# 02_CMUT_RX.net
KiCad netlist of a schematic drawn in Altium Designer
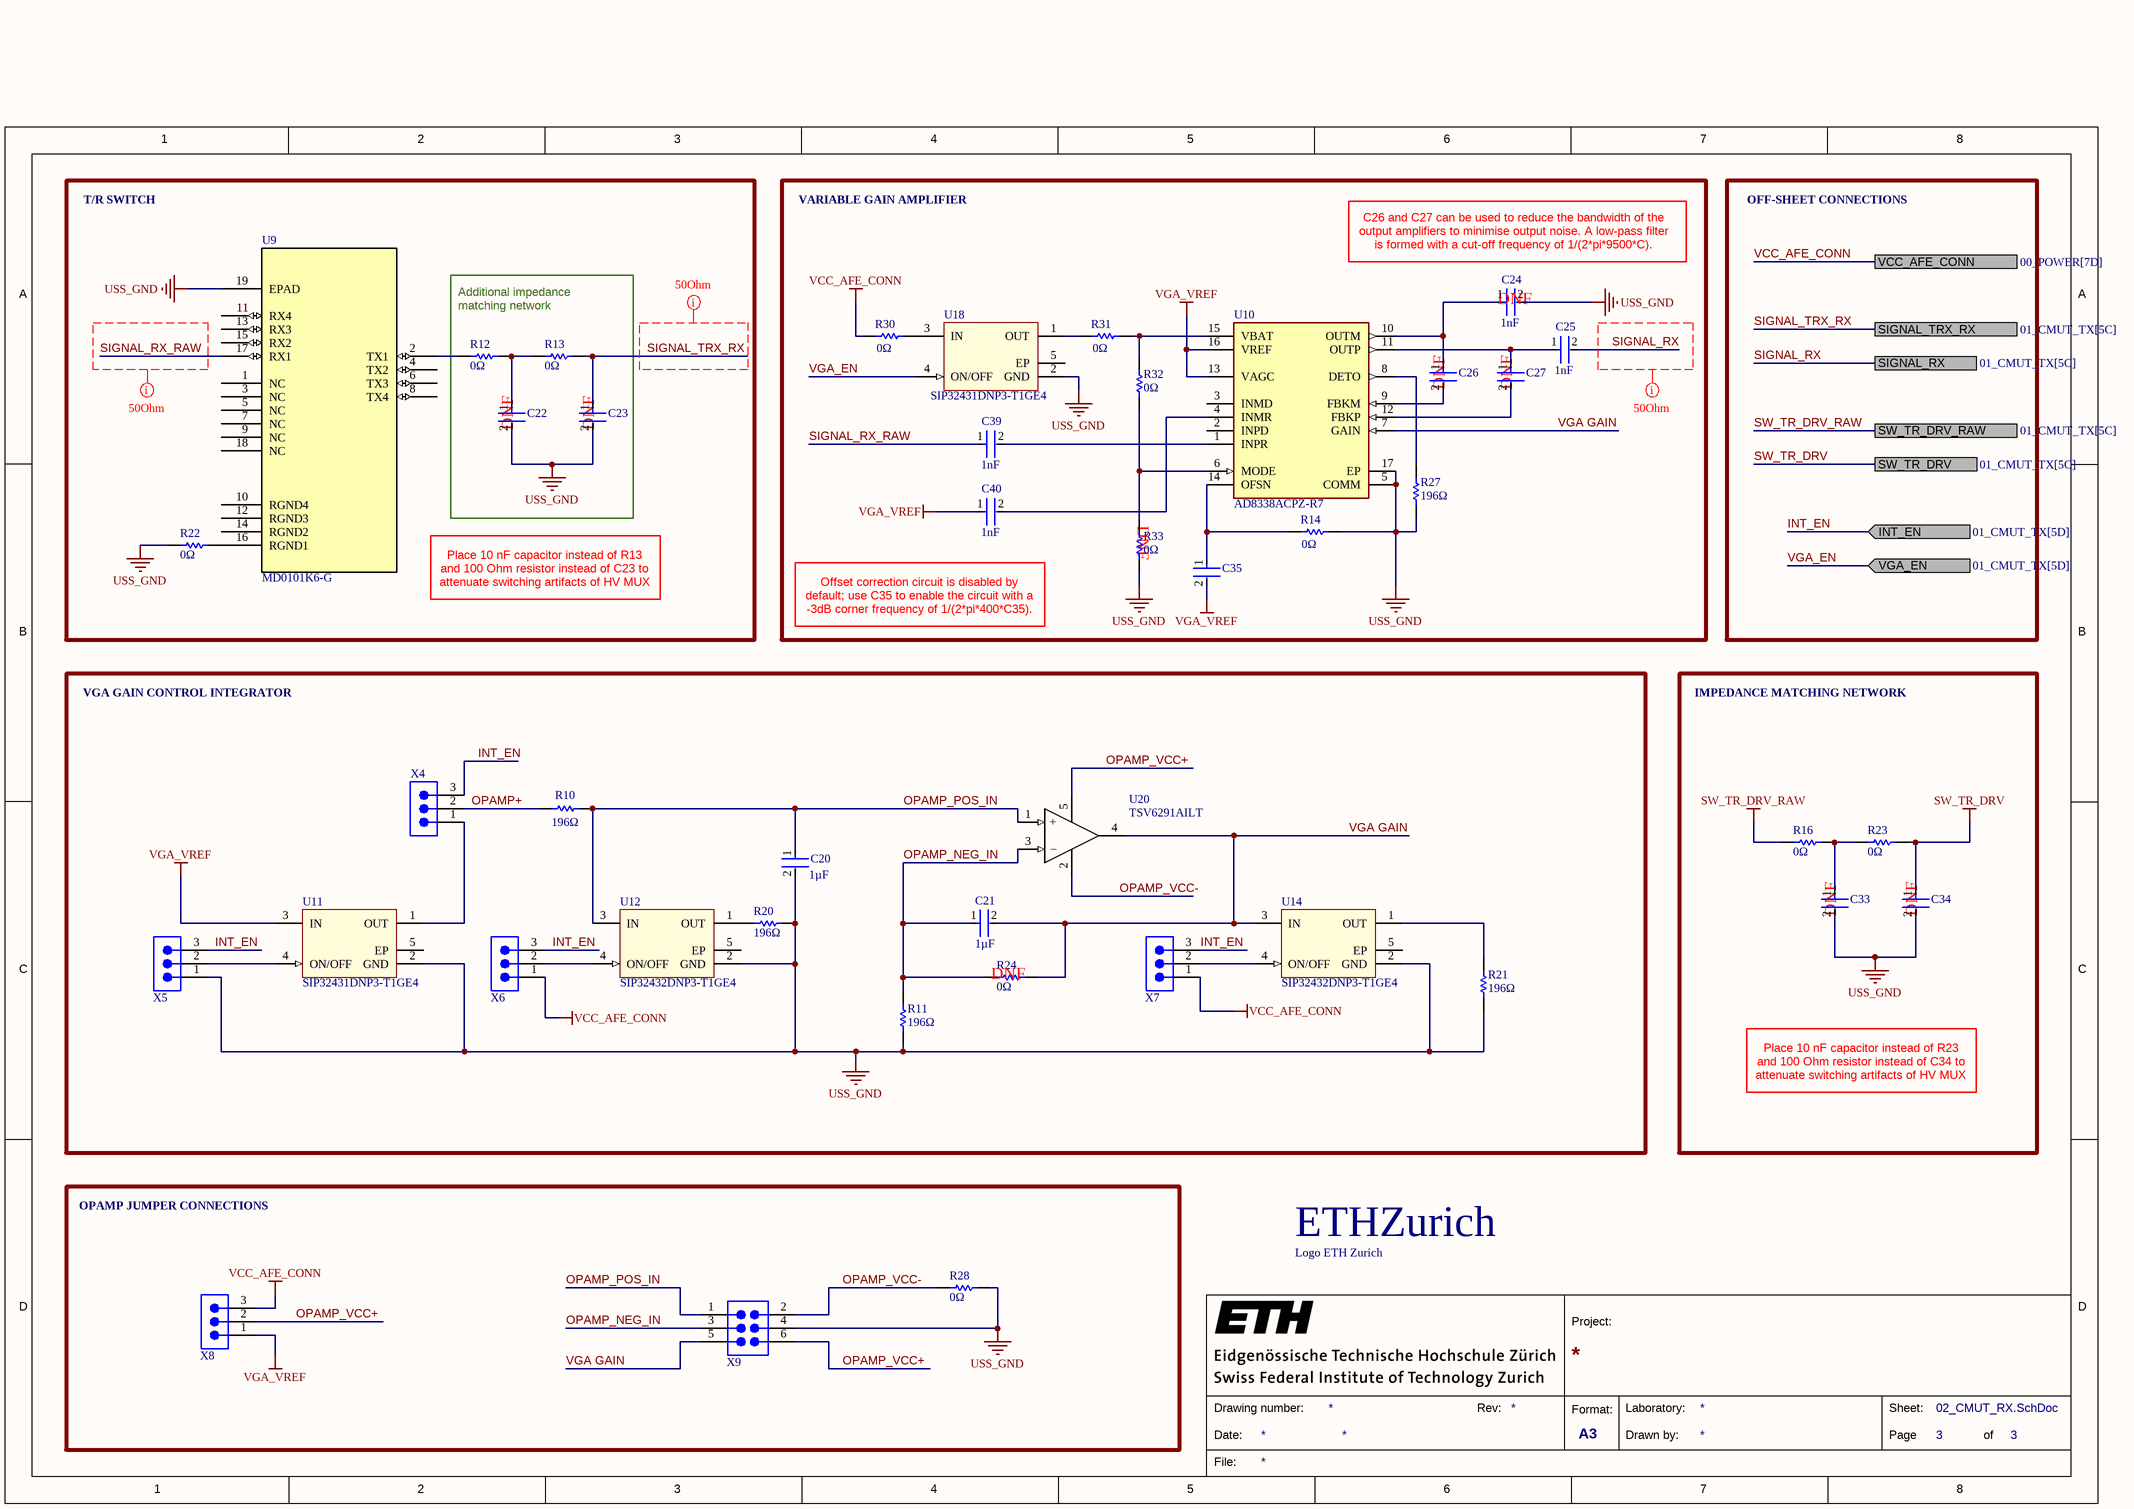
[diagram p0: 02_CMUT_RX.SchDoc]

(export (version "E")
  (design (tool "Eeschema 10.0.6"))
  (components
    (comp (ref "A1")
      (value "Logo ETH Zurich")
      (footprint "eth-zurich_4mm")
      (libsource (lib "ETHZ Vault") (part "Logo ETH Zurich"))
    )
    (comp (ref "C20")
      (value "CGA3E3X5R1H105K")
      (footprint "FP-CGA3E-0_3-0_1-IPC_B")
      (description "Cap Ceramic 1uF 50V X5R 10% Pad SMD 0603 +85°C Automotive T/R")
      (fields (field (name "TOLERANCE") "10%") (field (name "CAPACITANCE") "1µF"))
      (libsource (lib "Altium Content Vault") (part "b4654b650e69147ec39a6b967a45e02"))
    )
    (comp (ref "C21")
      (value "CGA3E3X5R1H105K")
      (footprint "FP-CGA3E-0_3-0_1-IPC_B")
      (description "Cap Ceramic 1uF 50V X5R 10% Pad SMD 0603 +85°C Automotive T/R")
      (fields (field (name "TOLERANCE") "10%") (field (name "CAPACITANCE") "1µF"))
      (libsource (lib "Altium Content Vault") (part "b4654b650e69147ec39a6b967a45e02"))
    )
    (comp (ref "C22")
      (value "CGA3E3X5R1H105K")
      (footprint "FP-CGA3E-0_3-0_1-IPC_B")
      (description "Cap Ceramic 1uF 50V X5R 10% Pad SMD 0603 +85°C Automotive T/R")
      (fields (field (name "TOLERANCE") "10%"))
      (libsource (lib "Altium Content Vault") (part "b4654b650e69147ec39a6b967a45e02"))
    )
    (comp (ref "C23")
      (value "CGA3E3X5R1H105K")
      (footprint "FP-CGA3E-0_3-0_1-IPC_B")
      (description "Cap Ceramic 1uF 50V X5R 10% Pad SMD 0603 +85°C Automotive T/R")
      (fields (field (name "TOLERANCE") "10%"))
      (libsource (lib "Altium Content Vault") (part "b4654b650e69147ec39a6b967a45e02"))
    )
    (comp (ref "C24")
      (value "TDK CGA3E2X5R1H102K080AA")
      (footprint "FP-CGA3E-0_3-0_1-IPC_A")
      (description "Cap Ceramic 1nF 50V X5R 10% Pad SMD 0603 +85°C Automotive T/R")
      (fields (field (name "TOLERANCE") "10%") (field (name "CAPACITANCE") "1nF"))
      (libsource (lib "Altium Content Vault") (part "b4654b650e69147ec39a6b967a45e02"))
    )
    (comp (ref "C25")
      (value "TDK CGA3E2X5R1H102K080AA")
      (footprint "FP-CGA3E-0_3-0_1-IPC_A")
      (description "Cap Ceramic 1nF 50V X5R 10% Pad SMD 0603 +85°C Automotive T/R")
      (fields (field (name "TOLERANCE") "10%") (field (name "CAPACITANCE") "1nF"))
      (libsource (lib "Altium Content Vault") (part "b4654b650e69147ec39a6b967a45e02"))
    )
    (comp (ref "C26")
      (value "CGA3E3X5R1H105K")
      (footprint "FP-CGA3E-0_3-0_1-IPC_B")
      (description "Cap Ceramic 1uF 50V X5R 10% Pad SMD 0603 +85°C Automotive T/R")
      (fields (field (name "TOLERANCE") "10%"))
      (libsource (lib "Altium Content Vault") (part "b4654b650e69147ec39a6b967a45e02"))
    )
    (comp (ref "C27")
      (value "CGA3E3X5R1H105K")
      (footprint "FP-CGA3E-0_3-0_1-IPC_B")
      (description "Cap Ceramic 1uF 50V X5R 10% Pad SMD 0603 +85°C Automotive T/R")
      (fields (field (name "TOLERANCE") "10%"))
      (libsource (lib "Altium Content Vault") (part "b4654b650e69147ec39a6b967a45e02"))
    )
    (comp (ref "C33")
      (value "CGA3E3X5R1H105K")
      (footprint "FP-CGA3E-0_3-0_1-IPC_B")
      (description "Cap Ceramic 1uF 50V X5R 10% Pad SMD 0603 +85°C Automotive T/R")
      (fields (field (name "TOLERANCE") "10%"))
      (libsource (lib "Altium Content Vault") (part "b4654b650e69147ec39a6b967a45e02"))
    )
    (comp (ref "C34")
      (value "CGA3E3X5R1H105K")
      (footprint "FP-CGA3E-0_3-0_1-IPC_B")
      (description "Cap Ceramic 1uF 50V X5R 10% Pad SMD 0603 +85°C Automotive T/R")
      (fields (field (name "TOLERANCE") "10%"))
      (libsource (lib "Altium Content Vault") (part "b4654b650e69147ec39a6b967a45e02"))
    )
    (comp (ref "C35")
      (value "CGA3E3X5R1H105K")
      (footprint "FP-CGA3E-0_3-0_1-IPC_B")
      (description "Cap Ceramic 1uF 50V X5R 10% Pad SMD 0603 +85°C Automotive T/R")
      (fields (field (name "TOLERANCE") "10%"))
      (libsource (lib "Altium Content Vault") (part "b4654b650e69147ec39a6b967a45e02"))
    )
    (comp (ref "C39")
      (value "TDK CGA3E2X5R1H102K080AA")
      (footprint "FP-CGA3E-0_3-0_1-IPC_A")
      (description "Cap Ceramic 1nF 50V X5R 10% Pad SMD 0603 +85°C Automotive T/R")
      (fields (field (name "TOLERANCE") "10%") (field (name "CAPACITANCE") "1nF"))
      (libsource (lib "Altium Content Vault") (part "b4654b650e69147ec39a6b967a45e02"))
    )
    (comp (ref "C40")
      (value "TDK CGA3E2X5R1H102K080AA")
      (footprint "FP-CGA3E-0_3-0_1-IPC_A")
      (description "Cap Ceramic 1nF 50V X5R 10% Pad SMD 0603 +85°C Automotive T/R")
      (fields (field (name "TOLERANCE") "10%") (field (name "CAPACITANCE") "1nF"))
      (libsource (lib "Altium Content Vault") (part "b4654b650e69147ec39a6b967a45e02"))
    )
    (comp (ref "R10")
      (value "RC0603FR-07196RL")
      (footprint "RESC1608X55X25NL10T15")
      (fields (field (name "MANUFACTURER") "Yageo") (field (name "RESISTANCE") "196Ω"))
      (libsource (lib "Altium Content Vault") (part "RES"))
    )
    (comp (ref "R11")
      (value "RC0603FR-07196RL")
      (footprint "RESC1608X55X25NL10T15")
      (fields (field (name "MANUFACTURER") "Yageo") (field (name "RESISTANCE") "196Ω"))
      (libsource (lib "Altium Content Vault") (part "RES"))
    )
    (comp (ref "R12")
      (value "RC0603JR-130RL")
      (footprint "RESC1608X55X25NL10T15")
      (fields (field (name "MANUFACTURER") "Yageo") (field (name "RESISTANCE") "0Ω"))
      (libsource (lib "Altium Content Vault") (part "RES"))
    )
    (comp (ref "R13")
      (value "RC0603JR-130RL")
      (footprint "RESC1608X55X25NL10T15")
      (fields (field (name "MANUFACTURER") "Yageo") (field (name "RESISTANCE") "0Ω"))
      (libsource (lib "Altium Content Vault") (part "RES"))
    )
    (comp (ref "R14")
      (value "RC0603JR-130RL")
      (footprint "RESC1608X55X25NL10T15")
      (fields (field (name "MANUFACTURER") "Yageo") (field (name "RESISTANCE") "0Ω"))
      (libsource (lib "Altium Content Vault") (part "RES"))
    )
    (comp (ref "R16")
      (value "RC0603JR-130RL")
      (footprint "RESC1608X55X25NL10T15")
      (fields (field (name "MANUFACTURER") "Yageo") (field (name "RESISTANCE") "0Ω"))
      (libsource (lib "Altium Content Vault") (part "RES"))
    )
    (comp (ref "R20")
      (value "RC0603FR-07196RL")
      (footprint "RESC1608X55X25NL10T15")
      (fields (field (name "MANUFACTURER") "Yageo") (field (name "RESISTANCE") "196Ω"))
      (libsource (lib "Altium Content Vault") (part "RES"))
    )
    (comp (ref "R21")
      (value "RC0603FR-07196RL")
      (footprint "RESC1608X55X25NL10T15")
      (fields (field (name "MANUFACTURER") "Yageo") (field (name "RESISTANCE") "196Ω"))
      (libsource (lib "Altium Content Vault") (part "RES"))
    )
    (comp (ref "R22")
      (value "RC0603JR-130RL")
      (footprint "RESC1608X55X25NL10T15")
      (fields (field (name "MANUFACTURER") "Yageo") (field (name "RESISTANCE") "0Ω"))
      (libsource (lib "Altium Content Vault") (part "RES"))
    )
    (comp (ref "R23")
      (value "RC0603JR-130RL")
      (footprint "RESC1608X55X25NL10T15")
      (fields (field (name "MANUFACTURER") "Yageo") (field (name "RESISTANCE") "0Ω"))
      (libsource (lib "Altium Content Vault") (part "RES"))
    )
    (comp (ref "R24")
      (value "RC0603JR-130RL")
      (footprint "RESC1608X55X25NL10T15")
      (fields (field (name "MANUFACTURER") "Yageo") (field (name "RESISTANCE") "0Ω"))
      (libsource (lib "Altium Content Vault") (part "RES"))
    )
    (comp (ref "R27")
      (value "RC0603FR-07196RL")
      (footprint "RESC1608X55X25NL10T15")
      (fields (field (name "MANUFACTURER") "Yageo") (field (name "RESISTANCE") "196Ω"))
      (libsource (lib "Altium Content Vault") (part "RES"))
    )
    (comp (ref "R28")
      (value "RC0603JR-130RL")
      (footprint "RESC1608X55X25NL10T15")
      (fields (field (name "MANUFACTURER") "Yageo") (field (name "RESISTANCE") "0Ω"))
      (libsource (lib "Altium Content Vault") (part "RES"))
    )
    (comp (ref "R30")
      (value "RC0603JR-130RL")
      (footprint "RESC1608X55X25NL10T15")
      (fields (field (name "MANUFACTURER") "Yageo") (field (name "RESISTANCE") "0Ω"))
      (libsource (lib "Altium Content Vault") (part "RES"))
    )
    (comp (ref "R31")
      (value "RC0603JR-130RL")
      (footprint "RESC1608X55X25NL10T15")
      (fields (field (name "MANUFACTURER") "Yageo") (field (name "RESISTANCE") "0Ω"))
      (libsource (lib "Altium Content Vault") (part "RES"))
    )
    (comp (ref "R32")
      (value "RC0603JR-130RL")
      (footprint "RESC1608X55X25NL10T15")
      (fields (field (name "MANUFACTURER") "Yageo") (field (name "RESISTANCE") "0Ω"))
      (libsource (lib "Altium Content Vault") (part "RES"))
    )
    (comp (ref "R33")
      (value "RC0603JR-130RL")
      (footprint "RESC1608X55X25NL10T15")
      (fields (field (name "MANUFACTURER") "Yageo") (field (name "RESISTANCE") "0Ω"))
      (libsource (lib "Altium Content Vault") (part "RES"))
    )
    (comp (ref "U9")
      (value "MD0101K6-G")
      (footprint "DFN18_5X5_MCH")
      (description "No Description Available")
      (fields (field (name "COPYRIGHT") "Copyright (C) 2022 Ultra Librarian. All rights reserved."))
      (libsource (lib "Schlib1") (part "MD0101K6-G"))
    )
    (comp (ref "U10")
      (value "AD8338ACPZ-R7")
      (footprint "FP-CP-16-22-IPC_C")
      (description "IC OPAMP VGA 1 CIRCUIT 16LFCSP")
      (fields
        (field (name "OCTOPART") "https://octopart.com/ad8338acpz-r7-analog+devices-21054770")
        (field (name "MANUFACTURER") "Analog Devices")
      )
      (libsource (lib "Altium Content Vault") (part "4ce7887af0b7713ffabab50ab6d8fb3"))
    )
    (comp (ref "U11")
      (value "SIP32431DNP3-T1GE4")
      (footprint "TDFN-4_V")
      (description "Power Switch ICs - Power Distribution 1A Slew Rate Ctrl Load Switch")
      (libsource (lib "ETHZ Vault") (part "SIP32431DNP3-T1GE4"))
    )
    (comp (ref "U12")
      (value "SIP32432DNP3-T1GE4")
      (footprint "TDFN-4_V")
      (description "Power Switch ICs - Power Distribution 1A Slew Rate Ctrl Load Switch")
      (libsource (lib "ETHZ Vault") (part "SIP32431DNP3-T1GE4"))
    )
    (comp (ref "U14")
      (value "SIP32432DNP3-T1GE4")
      (footprint "TDFN-4_V")
      (description "Power Switch ICs - Power Distribution 1A Slew Rate Ctrl Load Switch")
      (libsource (lib "ETHZ Vault") (part "SIP32431DNP3-T1GE4"))
    )
    (comp (ref "U18")
      (value "SIP32431DNP3-T1GE4")
      (footprint "TDFN-4_V")
      (description "Power Switch ICs - Power Distribution 1A Slew Rate Ctrl Load Switch")
      (libsource (lib "ETHZ Vault") (part "SIP32431DNP3-T1GE4"))
    )
    (comp (ref "U20")
      (value "TSV6291AILT")
      (footprint "SOT95P280X145-5N")
      (description "TVS6291A Series 5.5 V 1.3 MHz Single CMOS Operational Amplifier - SOT-23-5")
      (libsource (lib "Schlib1") (part "TSV6291AILT"))
    )
    (comp (ref "X4")
      (value "68000-103HLF")
      (footprint "68000-103HLF")
      (description "3 Positions Header, Unshrouded Connector 0.100\" (2.54mm) Through Hole Gold or Gold, GXT™")
      (fields (field (name "MANUFACTURER") "Amphenol FCI"))
      (libsource (lib "ETHZ Vault") (part "CON-1x3-Male"))
    )
    (comp (ref "X5")
      (value "68000-103HLF")
      (footprint "68000-103HLF")
      (description "3 Positions Header, Unshrouded Connector 0.100\" (2.54mm) Through Hole Gold or Gold, GXT™")
      (fields (field (name "MANUFACTURER") "Amphenol FCI"))
      (libsource (lib "ETHZ Vault") (part "CON-1x3-Male"))
    )
    (comp (ref "X6")
      (value "68000-103HLF")
      (footprint "68000-103HLF")
      (description "3 Positions Header, Unshrouded Connector 0.100\" (2.54mm) Through Hole Gold or Gold, GXT™")
      (fields (field (name "MANUFACTURER") "Amphenol FCI"))
      (libsource (lib "ETHZ Vault") (part "CON-1x3-Male"))
    )
    (comp (ref "X7")
      (value "68000-103HLF")
      (footprint "68000-103HLF")
      (description "3 Positions Header, Unshrouded Connector 0.100\" (2.54mm) Through Hole Gold or Gold, GXT™")
      (fields (field (name "MANUFACTURER") "Amphenol FCI"))
      (libsource (lib "ETHZ Vault") (part "CON-1x3-Male"))
    )
    (comp (ref "X8")
      (value "68000-103HLF")
      (footprint "68000-103HLF")
      (description "3 Positions Header, Unshrouded Connector 0.100\" (2.54mm) Through Hole Gold or Gold, GXT™")
      (fields (field (name "MANUFACTURER") "Amphenol FCI"))
      (libsource (lib "ETHZ Vault") (part "CON-1x3-Male"))
    )
    (comp (ref "X9")
      (value "67996-106HLF")
      (footprint "67996-106HLF")
      (description "6 Positions Header, Unshrouded Connector 0.100\" (2.54mm) Through Hole Gold or Gold, GXT™")
      (fields (field (name "MANUFACTURER") "Amphenol FCI"))
      (libsource (lib "ETHZ Vault") (part "CON-3x2-Male"))
    )
  )
  (nets
    (net (code "1") (name "/INT_EN") (class "Default")
      (node (ref "X4") (pin "3") (pinfunction "3_3") (pintype "passive"))
      (node (ref "X5") (pin "3") (pinfunction "3_3") (pintype "passive"))
      (node (ref "X6") (pin "3") (pinfunction "3_3") (pintype "passive"))
      (node (ref "X7") (pin "3") (pinfunction "3_3") (pintype "passive"))
    )
    (net (code "2") (name "/OPAMP+") (class "Default")
      (node (ref "R10") (pin "1") (pinfunction "1_1") (pintype "passive"))
      (node (ref "X4") (pin "2") (pinfunction "2_2") (pintype "passive"))
    )
    (net (code "3") (name "/OPAMP_NEG_IN") (class "Default")
      (node (ref "C21") (pin "1") (pinfunction "1_1") (pintype "passive"))
      (node (ref "R11") (pin "2") (pinfunction "2_2") (pintype "passive"))
      (node (ref "R24") (pin "2") (pinfunction "2_2") (pintype "passive"))
      (node (ref "U20") (pin "3") (pintype "input"))
      (node (ref "X9") (pin "3") (pinfunction "3_3") (pintype "passive"))
    )
    (net (code "4") (name "/OPAMP_POS_IN") (class "Default")
      (node (ref "C20") (pin "1") (pinfunction "1_1") (pintype "passive"))
      (node (ref "R10") (pin "2") (pinfunction "2_2") (pintype "passive"))
      (node (ref "U12") (pin "3") (pinfunction "IN_3") (pintype "power_in"))
      (node (ref "U20") (pin "1") (pintype "input"))
      (node (ref "X9") (pin "1") (pinfunction "1_1") (pintype "passive"))
    )
    (net (code "5") (name "/OPAMP_VCC+") (class "Default")
      (node (ref "U20") (pin "5") (pintype "power_in"))
      (node (ref "X8") (pin "2") (pinfunction "2_2") (pintype "passive"))
      (node (ref "X9") (pin "6") (pinfunction "6_6") (pintype "passive"))
    )
    (net (code "6") (name "/OPAMP_VCC-") (class "Default")
      (node (ref "R28") (pin "1") (pinfunction "1_1") (pintype "passive"))
      (node (ref "U20") (pin "2") (pintype "power_in"))
      (node (ref "X9") (pin "2") (pinfunction "2_2") (pintype "passive"))
    )
    (net (code "7") (name "/SIGNAL_RX") (class "Default")
      (node (ref "C25") (pin "2") (pinfunction "2_2") (pintype "passive"))
    )
    (net (code "8") (name "/SIGNAL_RX_RAW") (class "Default")
      (node (ref "C39") (pin "1") (pinfunction "1_1") (pintype "passive"))
      (node (ref "U9") (pin "17") (pinfunction "RX1_17") (pintype "bidirectional"))
    )
    (net (code "9") (name "/SIGNAL_TRX_RX") (class "Default")
      (node (ref "C23") (pin "1") (pinfunction "1_1") (pintype "passive"))
      (node (ref "R13") (pin "1") (pinfunction "1_1") (pintype "passive"))
    )
    (net (code "10") (name "/VGA GAIN") (class "Default")
      (node (ref "C21") (pin "2") (pinfunction "2_2") (pintype "passive"))
      (node (ref "R24") (pin "1") (pinfunction "1_1") (pintype "passive"))
      (node (ref "U10") (pin "7") (pinfunction "GAIN_7") (pintype "input"))
      (node (ref "U14") (pin "3") (pinfunction "IN_3") (pintype "power_in"))
      (node (ref "U20") (pin "4") (pintype "power_in"))
      (node (ref "X9") (pin "5") (pinfunction "5_5") (pintype "passive"))
    )
    (net (code "11") (name "/VGA_EN") (class "Default")
      (node (ref "U18") (pin "4") (pinfunction "ON/OFF_4") (pintype "input"))
    )
    (net (code "12") (name "Net-(C22-Pad1)") (class "Default")
      (node (ref "C22") (pin "1") (pinfunction "1_1") (pintype "passive"))
      (node (ref "R12") (pin "1") (pinfunction "1_1") (pintype "passive"))
      (node (ref "R13") (pin "2") (pinfunction "2_2") (pintype "passive"))
    )
    (net (code "13") (name "Net-(C33-Pad1)") (class "Default")
      (node (ref "C33") (pin "1") (pinfunction "1_1") (pintype "passive"))
      (node (ref "R16") (pin "1") (pinfunction "1_1") (pintype "passive"))
      (node (ref "R23") (pin "2") (pinfunction "2_2") (pintype "passive"))
    )
    (net (code "14") (name "Net-(U9-RGND1)") (class "Default")
      (node (ref "R22") (pin "1") (pinfunction "1_1") (pintype "passive"))
      (node (ref "U9") (pin "16") (pinfunction "RGND1_16") (pintype "passive"))
    )
    (net (code "15") (name "Net-(U9-TX1)") (class "Default")
      (node (ref "R12") (pin "2") (pinfunction "2_2") (pintype "passive"))
      (node (ref "U9") (pin "2") (pinfunction "TX1_2") (pintype "bidirectional"))
    )
    (net (code "16") (name "Net-(U10-DETO)") (class "Default")
      (node (ref "R27") (pin "1") (pinfunction "1_1") (pintype "passive"))
      (node (ref "U10") (pin "8") (pinfunction "DETO_8") (pintype "output"))
    )
    (net (code "17") (name "Net-(U10-FBKM)") (class "Default")
      (node (ref "C26") (pin "2") (pinfunction "2_2") (pintype "passive"))
      (node (ref "U10") (pin "9") (pinfunction "FBKM_9") (pintype "input"))
    )
    (net (code "18") (name "Net-(U10-FBKP)") (class "Default")
      (node (ref "C27") (pin "2") (pinfunction "2_2") (pintype "passive"))
      (node (ref "U10") (pin "12") (pinfunction "FBKP_12") (pintype "input"))
    )
    (net (code "19") (name "Net-(U10-INMR)") (class "Default")
      (node (ref "C40") (pin "2") (pinfunction "2_2") (pintype "passive"))
      (node (ref "U10") (pin "4") (pinfunction "INMR_4") (pintype "passive"))
    )
    (net (code "20") (name "Net-(U10-INPR)") (class "Default")
      (node (ref "C39") (pin "2") (pinfunction "2_2") (pintype "passive"))
      (node (ref "U10") (pin "1") (pinfunction "INPR_1") (pintype "passive"))
    )
    (net (code "21") (name "Net-(U10-MODE)") (class "Default")
      (node (ref "R32") (pin "2") (pinfunction "2_2") (pintype "passive"))
      (node (ref "R33") (pin "1") (pinfunction "1_1") (pintype "passive"))
      (node (ref "U10") (pin "6") (pinfunction "MODE_6") (pintype "input"))
    )
    (net (code "22") (name "Net-(U10-OFSN)") (class "Default")
      (node (ref "C35") (pin "1") (pinfunction "1_1") (pintype "passive"))
      (node (ref "R14") (pin "2") (pinfunction "2_2") (pintype "passive"))
      (node (ref "U10") (pin "14") (pinfunction "OFSN_14") (pintype "passive"))
    )
    (net (code "23") (name "Net-(U10-OUTM)") (class "Default")
      (node (ref "C24") (pin "1") (pinfunction "1_1") (pintype "passive"))
      (node (ref "C26") (pin "1") (pinfunction "1_1") (pintype "passive"))
      (node (ref "U10") (pin "10") (pinfunction "OUTM_10") (pintype "output"))
    )
    (net (code "24") (name "Net-(U10-OUTP)") (class "Default")
      (node (ref "C25") (pin "1") (pinfunction "1_1") (pintype "passive"))
      (node (ref "C27") (pin "1") (pinfunction "1_1") (pintype "passive"))
      (node (ref "U10") (pin "11") (pinfunction "OUTP_11") (pintype "output"))
    )
    (net (code "25") (name "Net-(U10-VBAT)") (class "Default")
      (node (ref "R31") (pin "1") (pinfunction "1_1") (pintype "passive"))
      (node (ref "R32") (pin "1") (pinfunction "1_1") (pintype "passive"))
      (node (ref "U10") (pin "15") (pinfunction "VBAT_15") (pintype "power_in"))
    )
    (net (code "26") (name "Net-(U11-ON{slash}OFF)") (class "Default")
      (node (ref "U11") (pin "4") (pinfunction "ON/OFF_4") (pintype "input"))
      (node (ref "X5") (pin "2") (pinfunction "2_2") (pintype "passive"))
    )
    (net (code "27") (name "Net-(U11-OUT)") (class "Default")
      (node (ref "U11") (pin "1") (pinfunction "OUT_1") (pintype "power_in"))
      (node (ref "X4") (pin "1") (pinfunction "1_1") (pintype "passive"))
    )
    (net (code "28") (name "Net-(U12-ON{slash}OFF)") (class "Default")
      (node (ref "U12") (pin "4") (pinfunction "ON/OFF_4") (pintype "input"))
      (node (ref "X6") (pin "2") (pinfunction "2_2") (pintype "passive"))
    )
    (net (code "29") (name "Net-(U12-OUT)") (class "Default")
      (node (ref "R20") (pin "2") (pinfunction "2_2") (pintype "passive"))
      (node (ref "U12") (pin "1") (pinfunction "OUT_1") (pintype "power_in"))
    )
    (net (code "30") (name "Net-(U14-ON{slash}OFF)") (class "Default")
      (node (ref "U14") (pin "4") (pinfunction "ON/OFF_4") (pintype "input"))
      (node (ref "X7") (pin "2") (pinfunction "2_2") (pintype "passive"))
    )
    (net (code "31") (name "Net-(U14-OUT)") (class "Default")
      (node (ref "R21") (pin "1") (pinfunction "1_1") (pintype "passive"))
      (node (ref "U14") (pin "1") (pinfunction "OUT_1") (pintype "power_in"))
    )
    (net (code "32") (name "Net-(U18-IN)") (class "Default")
      (node (ref "R30") (pin "1") (pinfunction "1_1") (pintype "passive"))
      (node (ref "U18") (pin "3") (pinfunction "IN_3") (pintype "power_in"))
    )
    (net (code "33") (name "Net-(U18-OUT)") (class "Default")
      (node (ref "R31") (pin "2") (pinfunction "2_2") (pintype "passive"))
      (node (ref "U18") (pin "1") (pinfunction "OUT_1") (pintype "power_in"))
    )
    (net (code "34") (name "SW_TR_DRV") (class "Default")
      (node (ref "C34") (pin "1") (pinfunction "1_1") (pintype "passive"))
      (node (ref "R23") (pin "1") (pinfunction "1_1") (pintype "passive"))
    )
    (net (code "35") (name "SW_TR_DRV_RAW") (class "Default")
      (node (ref "R16") (pin "2") (pinfunction "2_2") (pintype "passive"))
    )
    (net (code "36") (name "USS_GND") (class "Default")
      (node (ref "C20") (pin "2") (pinfunction "2_2") (pintype "passive"))
      (node (ref "C22") (pin "2") (pinfunction "2_2") (pintype "passive"))
      (node (ref "C23") (pin "2") (pinfunction "2_2") (pintype "passive"))
      (node (ref "C24") (pin "2") (pinfunction "2_2") (pintype "passive"))
      (node (ref "C33") (pin "2") (pinfunction "2_2") (pintype "passive"))
      (node (ref "C34") (pin "2") (pinfunction "2_2") (pintype "passive"))
      (node (ref "R11") (pin "1") (pinfunction "1_1") (pintype "passive"))
      (node (ref "R14") (pin "1") (pinfunction "1_1") (pintype "passive"))
      (node (ref "R20") (pin "1") (pinfunction "1_1") (pintype "passive"))
      (node (ref "R21") (pin "2") (pinfunction "2_2") (pintype "passive"))
      (node (ref "R22") (pin "2") (pinfunction "2_2") (pintype "passive"))
      (node (ref "R27") (pin "2") (pinfunction "2_2") (pintype "passive"))
      (node (ref "R28") (pin "2") (pinfunction "2_2") (pintype "passive"))
      (node (ref "R33") (pin "2") (pinfunction "2_2") (pintype "passive"))
      (node (ref "U10") (pin "17") (pinfunction "EP_17") (pintype "power_in"))
      (node (ref "U10") (pin "5") (pinfunction "COMM_5") (pintype "power_in"))
      (node (ref "U11") (pin "2") (pinfunction "GND_2") (pintype "power_in"))
      (node (ref "U12") (pin "2") (pinfunction "GND_2") (pintype "power_in"))
      (node (ref "U14") (pin "2") (pinfunction "GND_2") (pintype "power_in"))
      (node (ref "U18") (pin "2") (pinfunction "GND_2") (pintype "power_in"))
      (node (ref "U9") (pin "19") (pinfunction "EPAD_19") (pintype "passive"))
      (node (ref "X5") (pin "1") (pinfunction "1_1") (pintype "passive"))
      (node (ref "X9") (pin "4") (pinfunction "4_4") (pintype "passive"))
    )
    (net (code "37") (name "VCC_AFE_CONN") (class "Default")
      (node (ref "R30") (pin "2") (pinfunction "2_2") (pintype "passive"))
      (node (ref "X6") (pin "1") (pinfunction "1_1") (pintype "passive"))
      (node (ref "X7") (pin "1") (pinfunction "1_1") (pintype "passive"))
      (node (ref "X8") (pin "3") (pinfunction "3_3") (pintype "passive"))
    )
    (net (code "38") (name "VGA_VREF") (class "Default")
      (node (ref "C35") (pin "2") (pinfunction "2_2") (pintype "passive"))
      (node (ref "C40") (pin "1") (pinfunction "1_1") (pintype "passive"))
      (node (ref "U10") (pin "13") (pinfunction "VAGC_13") (pintype "power_in"))
      (node (ref "U10") (pin "16") (pinfunction "VREF_16") (pintype "power_in"))
      (node (ref "U11") (pin "3") (pinfunction "IN_3") (pintype "power_in"))
      (node (ref "X8") (pin "1") (pinfunction "1_1") (pintype "passive"))
    )
    (net (code "39") (name "unconnected-(U9-NC-Pad1)") (class "Default")
      (node (ref "U9") (pin "1") (pinfunction "NC_1") (pintype "passive"))
    )
    (net (code "40") (name "unconnected-(U9-NC-Pad3)") (class "Default")
      (node (ref "U9") (pin "3") (pinfunction "NC_3") (pintype "passive"))
    )
    (net (code "41") (name "unconnected-(U9-NC-Pad5)") (class "Default")
      (node (ref "U9") (pin "5") (pinfunction "NC_5") (pintype "passive"))
    )
    (net (code "42") (name "unconnected-(U9-NC-Pad7)") (class "Default")
      (node (ref "U9") (pin "7") (pinfunction "NC_7") (pintype "passive"))
    )
    (net (code "43") (name "unconnected-(U9-NC-Pad9)") (class "Default")
      (node (ref "U9") (pin "9") (pinfunction "NC_9") (pintype "passive"))
    )
    (net (code "44") (name "unconnected-(U9-NC-Pad18)") (class "Default")
      (node (ref "U9") (pin "18") (pinfunction "NC_18") (pintype "passive"))
    )
    (net (code "45") (name "unconnected-(U9-RGND2-Pad14)") (class "Default")
      (node (ref "U9") (pin "14") (pinfunction "RGND2_14") (pintype "passive"))
    )
    (net (code "46") (name "unconnected-(U9-RGND3-Pad12)") (class "Default")
      (node (ref "U9") (pin "12") (pinfunction "RGND3_12") (pintype "passive"))
    )
    (net (code "47") (name "unconnected-(U9-RGND4-Pad10)") (class "Default")
      (node (ref "U9") (pin "10") (pinfunction "RGND4_10") (pintype "passive"))
    )
    (net (code "48") (name "unconnected-(U9-RX2-Pad15)") (class "Default")
      (node (ref "U9") (pin "15") (pinfunction "RX2_15") (pintype "bidirectional"))
    )
    (net (code "49") (name "unconnected-(U9-RX3-Pad13)") (class "Default")
      (node (ref "U9") (pin "13") (pinfunction "RX3_13") (pintype "bidirectional"))
    )
    (net (code "50") (name "unconnected-(U9-RX4-Pad11)") (class "Default")
      (node (ref "U9") (pin "11") (pinfunction "RX4_11") (pintype "bidirectional"))
    )
    (net (code "51") (name "unconnected-(U9-TX2-Pad4)") (class "Default")
      (node (ref "U9") (pin "4") (pinfunction "TX2_4") (pintype "bidirectional"))
    )
    (net (code "52") (name "unconnected-(U9-TX3-Pad6)") (class "Default")
      (node (ref "U9") (pin "6") (pinfunction "TX3_6") (pintype "bidirectional"))
    )
    (net (code "53") (name "unconnected-(U9-TX4-Pad8)") (class "Default")
      (node (ref "U9") (pin "8") (pinfunction "TX4_8") (pintype "bidirectional"))
    )
    (net (code "54") (name "unconnected-(U10-INMD-Pad3)") (class "Default")
      (node (ref "U10") (pin "3") (pinfunction "INMD_3") (pintype "passive"))
    )
    (net (code "55") (name "unconnected-(U10-INPD-Pad2)") (class "Default")
      (node (ref "U10") (pin "2") (pinfunction "INPD_2") (pintype "passive"))
    )
    (net (code "56") (name "unconnected-(U11-EP-Pad5)") (class "Default")
      (node (ref "U11") (pin "5") (pinfunction "EP_5") (pintype "power_in"))
    )
    (net (code "57") (name "unconnected-(U12-EP-Pad5)") (class "Default")
      (node (ref "U12") (pin "5") (pinfunction "EP_5") (pintype "power_in"))
    )
    (net (code "58") (name "unconnected-(U14-EP-Pad5)") (class "Default")
      (node (ref "U14") (pin "5") (pinfunction "EP_5") (pintype "power_in"))
    )
    (net (code "59") (name "unconnected-(U18-EP-Pad5)") (class "Default")
      (node (ref "U18") (pin "5") (pinfunction "EP_5") (pintype "power_in"))
    )
  )
)
